# front_pcb.net
KiCad netlist of a schematic drawn in EAGLE
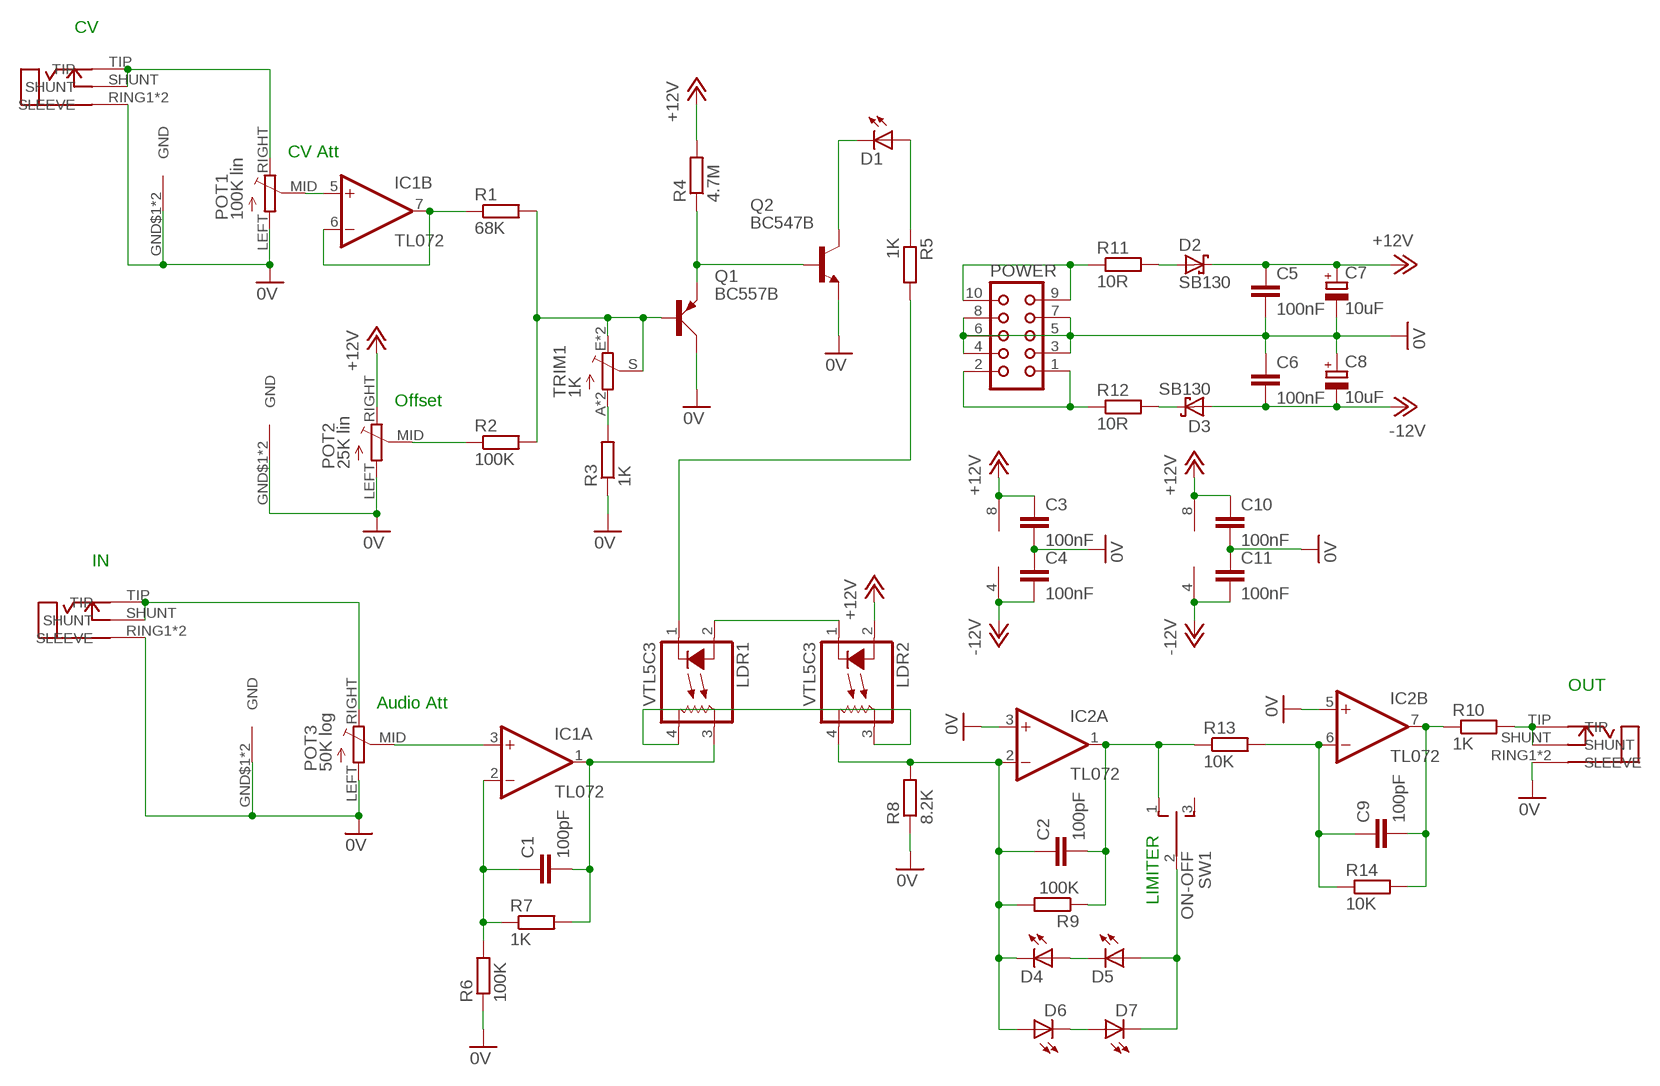
[diagram p0: schematic, sheet 1]

(export (version "E")
  (design (tool "Eeschema 10.0.6"))
  (components
    (comp (ref "C1")
      (value "100pF")
      (footprint "eagle-import:C025-024X044")
      (libsource (lib "eagle-import") (part "C-EU025-024X044"))
    )
    (comp (ref "C2")
      (value "100pF")
      (footprint "eagle-import:C025-024X044")
      (libsource (lib "eagle-import") (part "C-EU025-024X044"))
    )
    (comp (ref "C3")
      (value "100nF")
      (footprint "eagle-import:C025-024X044")
      (libsource (lib "eagle-import") (part "C-EU025-024X044"))
    )
    (comp (ref "C4")
      (value "100nF")
      (footprint "eagle-import:C025-024X044")
      (libsource (lib "eagle-import") (part "C-EU025-024X044"))
    )
    (comp (ref "C5")
      (value "100nF")
      (footprint "eagle-import:C025-024X044")
      (libsource (lib "eagle-import") (part "C-EU025-024X044"))
    )
    (comp (ref "C6")
      (value "100nF")
      (footprint "eagle-import:C025-024X044")
      (libsource (lib "eagle-import") (part "C-EU025-024X044"))
    )
    (comp (ref "C7")
      (value "10uF")
      (footprint "eagle-import:E2-5")
      (libsource (lib "eagle-import") (part "CPOL-EUE2-5"))
    )
    (comp (ref "C8")
      (value "10uF")
      (footprint "eagle-import:E2-5")
      (libsource (lib "eagle-import") (part "CPOL-EUE2-5"))
    )
    (comp (ref "C9")
      (value "100pF")
      (footprint "eagle-import:C025-024X044")
      (libsource (lib "eagle-import") (part "C-EU025-024X044"))
    )
    (comp (ref "C10")
      (value "100nF")
      (footprint "eagle-import:C025-024X044")
      (libsource (lib "eagle-import") (part "C-EU025-024X044"))
    )
    (comp (ref "C11")
      (value "100nF")
      (footprint "eagle-import:C025-024X044")
      (libsource (lib "eagle-import") (part "C-EU025-024X044"))
    )
    (comp (ref "CV")
      (value "ERTHENVAR_3.5MM_JACK")
      (footprint "eagle-import:ERTHENVAR")
      (libsource (lib "eagle-import") (part "ERTHENVAR_3.5MM_JACK"))
    )
    (comp (ref "D1")
      (value "LED3MM")
      (footprint "eagle-import:LED3MM")
      (libsource (lib "eagle-import") (part "LED3MM"))
    )
    (comp (ref "D2")
      (value "SB130")
      (footprint "eagle-import:DO41-7")
      (libsource (lib "eagle-import") (part "SB130DO-204AL"))
    )
    (comp (ref "D3")
      (value "SB130")
      (footprint "eagle-import:DO41-7")
      (libsource (lib "eagle-import") (part "SB130DO-204AL"))
    )
    (comp (ref "D4")
      (value "LED3MM")
      (footprint "eagle-import:LED3MM")
      (libsource (lib "eagle-import") (part "LED3MM"))
    )
    (comp (ref "D5")
      (value "LED3MM")
      (footprint "eagle-import:LED3MM")
      (libsource (lib "eagle-import") (part "LED3MM"))
    )
    (comp (ref "D6")
      (value "LED3MM")
      (footprint "eagle-import:LED3MM")
      (libsource (lib "eagle-import") (part "LED3MM"))
    )
    (comp (ref "D7")
      (value "LED3MM")
      (footprint "eagle-import:LED3MM")
      (libsource (lib "eagle-import") (part "LED3MM"))
    )
    (comp (ref "IC1")
      (value "TL072")
      (footprint "eagle-import:DIL08")
      (libsource (lib "eagle-import") (part "TL072P"))
    )
    (comp (ref "IC2")
      (value "TL072")
      (footprint "eagle-import:DIL08")
      (libsource (lib "eagle-import") (part "TL072P"))
    )
    (comp (ref "IN")
      (value "ERTHENVAR_3.5MM_JACK")
      (footprint "eagle-import:ERTHENVAR")
      (libsource (lib "eagle-import") (part "ERTHENVAR_3.5MM_JACK"))
    )
    (comp (ref "LDR1")
      (value "VTL5C3")
      (footprint "eagle-import:VTL5C")
      (fields (field (name "MF") "VACTEC PHOTO") (field (name "MPN") "VTL5C9"))
      (libsource (lib "eagle-import") (part "VTL5C9"))
    )
    (comp (ref "LDR2")
      (value "VTL5C3")
      (footprint "eagle-import:VTL5C")
      (fields (field (name "MF") "VACTEC PHOTO") (field (name "MPN") "VTL5C9"))
      (libsource (lib "eagle-import") (part "VTL5C9"))
    )
    (comp (ref "OUT")
      (value "ERTHENVAR_3.5MM_JACK")
      (footprint "eagle-import:ERTHENVAR")
      (libsource (lib "eagle-import") (part "ERTHENVAR_3.5MM_JACK"))
    )
    (comp (ref "POT1")
      (value "100K lin")
      (footprint "eagle-import:POT-ALPHA9")
      (libsource (lib "eagle-import") (part "POT-ALPHA9"))
    )
    (comp (ref "POT2")
      (value "25K lin")
      (footprint "eagle-import:POT-ALPHA9")
      (libsource (lib "eagle-import") (part "POT-ALPHA9"))
    )
    (comp (ref "POT3")
      (value "50K log")
      (footprint "eagle-import:POT-ALPHA9")
      (libsource (lib "eagle-import") (part "POT-ALPHA9"))
    )
    (comp (ref "POWER")
      (value "CON10L")
      (footprint "eagle-import:CON10L")
      (libsource (lib "eagle-import") (part "CON10L"))
    )
    (comp (ref "Q1")
      (value "BC557B")
      (footprint "eagle-import:TO92-LINE")
      (libsource (lib "eagle-import") (part "BC557TO92-LINE"))
    )
    (comp (ref "Q2")
      (value "BC547B")
      (footprint "eagle-import:TO92-LINE")
      (libsource (lib "eagle-import") (part "BC547TO92-LINE"))
    )
    (comp (ref "R1")
      (value "68K")
      (footprint "eagle-import:0207_9")
      (libsource (lib "eagle-import") (part "R-EU_0207/10"))
    )
    (comp (ref "R2")
      (value "100K")
      (footprint "eagle-import:0207_9")
      (libsource (lib "eagle-import") (part "R-EU_0207/10"))
    )
    (comp (ref "R3")
      (value "1K")
      (footprint "eagle-import:0207_9")
      (libsource (lib "eagle-import") (part "R-EU_0207/10"))
    )
    (comp (ref "R4")
      (value "4.7M")
      (footprint "eagle-import:0207_9")
      (libsource (lib "eagle-import") (part "R-EU_0207/10"))
    )
    (comp (ref "R5")
      (value "1K")
      (footprint "eagle-import:0207_9")
      (libsource (lib "eagle-import") (part "R-EU_0207/10"))
    )
    (comp (ref "R6")
      (value "100K")
      (footprint "eagle-import:0207_9")
      (libsource (lib "eagle-import") (part "R-EU_0207/10"))
    )
    (comp (ref "R7")
      (value "1K")
      (footprint "eagle-import:0207_9")
      (libsource (lib "eagle-import") (part "R-EU_0207/10"))
    )
    (comp (ref "R8")
      (value "8.2K")
      (footprint "eagle-import:0207_9")
      (libsource (lib "eagle-import") (part "R-EU_0207/10"))
    )
    (comp (ref "R9")
      (value "100K")
      (footprint "eagle-import:0207_9")
      (libsource (lib "eagle-import") (part "R-EU_0207/10"))
    )
    (comp (ref "R10")
      (value "1K")
      (footprint "eagle-import:0207_9")
      (libsource (lib "eagle-import") (part "R-EU_0207/10"))
    )
    (comp (ref "R11")
      (value "10R")
      (footprint "eagle-import:0207_9")
      (libsource (lib "eagle-import") (part "R-EU_0207/10"))
    )
    (comp (ref "R12")
      (value "10R")
      (footprint "eagle-import:0207_9")
      (libsource (lib "eagle-import") (part "R-EU_0207/10"))
    )
    (comp (ref "R13")
      (value "10K")
      (footprint "eagle-import:0207_9")
      (libsource (lib "eagle-import") (part "R-EU_0207/10"))
    )
    (comp (ref "R14")
      (value "10K")
      (footprint "eagle-import:0207_9")
      (libsource (lib "eagle-import") (part "R-EU_0207/10"))
    )
    (comp (ref "SW1")
      (value "ON-OFF")
      (footprint "eagle-import:SPDT-HORIZONTAL-TOP-SUBMINI-MULTICOMP")
      (libsource (lib "eagle-import") (part "SPDTTOP-SUBMINI"))
    )
    (comp (ref "TRIM1")
      (value "1K")
      (footprint "eagle-import:B25P")
      (libsource (lib "eagle-import") (part "TRIM_EU-B25P"))
    )
  )
  (nets
    (net (code "1") (name "+12V") (class "Default")
      (node (ref "C10") (pin "1") (pinfunction "1_1") (pintype "passive"))
      (node (ref "C3") (pin "1") (pinfunction "1_1") (pintype "passive"))
      (node (ref "C5") (pin "1") (pinfunction "1_1") (pintype "passive"))
      (node (ref "C7") (pin "+") (pinfunction "+_+") (pintype "passive"))
      (node (ref "D2") (pin "C") (pinfunction "C_C") (pintype "passive"))
      (node (ref "IC1") (pin "8") (pinfunction "V+_8") (pintype "power_in"))
      (node (ref "IC2") (pin "8") (pinfunction "V+_8") (pintype "power_in"))
      (node (ref "LDR2") (pin "2") (pinfunction "A_2") (pintype "passive"))
      (node (ref "POT2") (pin "RIGHT") (pinfunction "RIGHT_RIGHT") (pintype "passive"))
      (node (ref "R4") (pin "2") (pinfunction "2_2") (pintype "passive"))
    )
    (net (code "2") (name "-12V") (class "Default")
      (node (ref "C11") (pin "2") (pinfunction "2_2") (pintype "passive"))
      (node (ref "C4") (pin "2") (pinfunction "2_2") (pintype "passive"))
      (node (ref "C6") (pin "2") (pinfunction "2_2") (pintype "passive"))
      (node (ref "C8") (pin "-") (pinfunction "-_-") (pintype "passive"))
      (node (ref "D3") (pin "A") (pinfunction "A_A") (pintype "passive"))
      (node (ref "IC1") (pin "4") (pinfunction "V-_4") (pintype "power_in"))
      (node (ref "IC2") (pin "4") (pinfunction "V-_4") (pintype "power_in"))
    )
    (net (code "3") (name "0V") (class "Default")
      (node (ref "C10") (pin "2") (pinfunction "2_2") (pintype "passive"))
      (node (ref "C11") (pin "1") (pinfunction "1_1") (pintype "passive"))
      (node (ref "C3") (pin "2") (pinfunction "2_2") (pintype "passive"))
      (node (ref "C4") (pin "1") (pinfunction "1_1") (pintype "passive"))
      (node (ref "C5") (pin "2") (pinfunction "2_2") (pintype "passive"))
      (node (ref "C6") (pin "1") (pinfunction "1_1") (pintype "passive"))
      (node (ref "C7") (pin "-") (pinfunction "-_-") (pintype "passive"))
      (node (ref "C8") (pin "+") (pinfunction "+_+") (pintype "passive"))
      (node (ref "CV") (pin "RING1") (pinfunction "SLEEVE_RING1") (pintype "bidirectional"))
      (node (ref "CV") (pin "RING2") (pinfunction "SLEEVE_RING2") (pintype "bidirectional"))
      (node (ref "IC2") (pin "3") (pinfunction "+IN_3") (pintype "input"))
      (node (ref "IC2") (pin "5") (pinfunction "+IN_5") (pintype "input"))
      (node (ref "IN") (pin "RING1") (pinfunction "SLEEVE_RING1") (pintype "bidirectional"))
      (node (ref "IN") (pin "RING2") (pinfunction "SLEEVE_RING2") (pintype "bidirectional"))
      (node (ref "OUT") (pin "RING1") (pinfunction "SLEEVE_RING1") (pintype "bidirectional"))
      (node (ref "OUT") (pin "RING2") (pinfunction "SLEEVE_RING2") (pintype "bidirectional"))
      (node (ref "POT1") (pin "GND$1") (pinfunction "GND_GND$1") (pintype "bidirectional"))
      (node (ref "POT1") (pin "GND$2") (pinfunction "GND_GND$2") (pintype "bidirectional"))
      (node (ref "POT1") (pin "LEFT") (pinfunction "LEFT_LEFT") (pintype "passive"))
      (node (ref "POT2") (pin "GND$1") (pinfunction "GND_GND$1") (pintype "bidirectional"))
      (node (ref "POT2") (pin "GND$2") (pinfunction "GND_GND$2") (pintype "bidirectional"))
      (node (ref "POT2") (pin "LEFT") (pinfunction "LEFT_LEFT") (pintype "passive"))
      (node (ref "POT3") (pin "GND$1") (pinfunction "GND_GND$1") (pintype "bidirectional"))
      (node (ref "POT3") (pin "GND$2") (pinfunction "GND_GND$2") (pintype "bidirectional"))
      (node (ref "POT3") (pin "LEFT") (pinfunction "LEFT_LEFT") (pintype "passive"))
      (node (ref "POWER") (pin "3") (pinfunction "3_3") (pintype "passive"))
      (node (ref "POWER") (pin "4") (pinfunction "4_4") (pintype "passive"))
      (node (ref "POWER") (pin "5") (pinfunction "5_5") (pintype "passive"))
      (node (ref "POWER") (pin "6") (pinfunction "6_6") (pintype "passive"))
      (node (ref "POWER") (pin "7") (pinfunction "7_7") (pintype "passive"))
      (node (ref "POWER") (pin "8") (pinfunction "8_8") (pintype "passive"))
      (node (ref "Q1") (pin "3") (pinfunction "C_3") (pintype "passive"))
      (node (ref "Q2") (pin "1") (pinfunction "E_1") (pintype "passive"))
      (node (ref "R3") (pin "1") (pinfunction "1_1") (pintype "passive"))
      (node (ref "R6") (pin "1") (pinfunction "1_1") (pintype "passive"))
      (node (ref "R8") (pin "1") (pinfunction "1_1") (pintype "passive"))
    )
    (net (code "4") (name "Net-(CV-PadSHUNT)") (class "Default")
      (node (ref "CV") (pin "SHUNT") (pinfunction "SHUNT_SHUNT") (pintype "bidirectional"))
      (node (ref "CV") (pin "TIP") (pinfunction "TIP_TIP") (pintype "bidirectional"))
      (node (ref "POT1") (pin "RIGHT") (pinfunction "RIGHT_RIGHT") (pintype "passive"))
    )
    (net (code "5") (name "Net-(D1-C)") (class "Default")
      (node (ref "D1") (pin "K") (pinfunction "C_K") (pintype "passive"))
      (node (ref "Q2") (pin "3") (pinfunction "C_3") (pintype "passive"))
    )
    (net (code "6") (name "Net-(D1-PadA)") (class "Default")
      (node (ref "D1") (pin "A") (pinfunction "A_A") (pintype "passive"))
      (node (ref "R5") (pin "1") (pinfunction "1_1") (pintype "passive"))
    )
    (net (code "7") (name "Net-(D2-PadA)") (class "Default")
      (node (ref "D2") (pin "A") (pinfunction "A_A") (pintype "passive"))
      (node (ref "R11") (pin "2") (pinfunction "2_2") (pintype "passive"))
    )
    (net (code "8") (name "Net-(D3-PadC)") (class "Default")
      (node (ref "D3") (pin "C") (pinfunction "C_C") (pintype "passive"))
      (node (ref "R12") (pin "2") (pinfunction "2_2") (pintype "passive"))
    )
    (net (code "9") (name "Net-(D4-C)") (class "Default")
      (node (ref "C2") (pin "1") (pinfunction "1_1") (pintype "passive"))
      (node (ref "D4") (pin "K") (pinfunction "C_K") (pintype "passive"))
      (node (ref "D6") (pin "A") (pinfunction "A_A") (pintype "passive"))
      (node (ref "IC2") (pin "2") (pinfunction "-IN_2") (pintype "input"))
      (node (ref "LDR2") (pin "4") (pinfunction "L2_4") (pintype "passive"))
      (node (ref "R8") (pin "2") (pinfunction "2_2") (pintype "passive"))
      (node (ref "R9") (pin "2") (pinfunction "2_2") (pintype "passive"))
    )
    (net (code "10") (name "Net-(D5-C)") (class "Default")
      (node (ref "D4") (pin "A") (pinfunction "A_A") (pintype "passive"))
      (node (ref "D5") (pin "K") (pinfunction "C_K") (pintype "passive"))
    )
    (net (code "11") (name "Net-(D6-C)") (class "Default")
      (node (ref "D6") (pin "K") (pinfunction "C_K") (pintype "passive"))
      (node (ref "D7") (pin "A") (pinfunction "A_A") (pintype "passive"))
    )
    (net (code "12") (name "Net-(D7-C)") (class "Default")
      (node (ref "D5") (pin "A") (pinfunction "A_A") (pintype "passive"))
      (node (ref "D7") (pin "K") (pinfunction "C_K") (pintype "passive"))
      (node (ref "SW1") (pin "2") (pinfunction "2_2") (pintype "passive"))
    )
    (net (code "13") (name "Net-(IC1A-+IN)") (class "Default")
      (node (ref "IC1") (pin "3") (pinfunction "+IN_3") (pintype "input"))
      (node (ref "POT3") (pin "MID") (pinfunction "MID_MID") (pintype "passive"))
    )
    (net (code "14") (name "Net-(IC1A--IN)") (class "Default")
      (node (ref "C1") (pin "1") (pinfunction "1_1") (pintype "passive"))
      (node (ref "IC1") (pin "2") (pinfunction "-IN_2") (pintype "input"))
      (node (ref "R6") (pin "2") (pinfunction "2_2") (pintype "passive"))
      (node (ref "R7") (pin "1") (pinfunction "1_1") (pintype "passive"))
    )
    (net (code "15") (name "Net-(IC1A-OUT)") (class "Default")
      (node (ref "C1") (pin "2") (pinfunction "2_2") (pintype "passive"))
      (node (ref "IC1") (pin "1") (pinfunction "OUT_1") (pintype "output"))
      (node (ref "LDR1") (pin "3") (pinfunction "L1_3") (pintype "passive"))
      (node (ref "R7") (pin "2") (pinfunction "2_2") (pintype "passive"))
    )
    (net (code "16") (name "Net-(IC1B-+IN)") (class "Default")
      (node (ref "IC1") (pin "5") (pinfunction "+IN_5") (pintype "input"))
      (node (ref "POT1") (pin "MID") (pinfunction "MID_MID") (pintype "passive"))
    )
    (net (code "17") (name "Net-(IC1B--IN)") (class "Default")
      (node (ref "IC1") (pin "6") (pinfunction "-IN_6") (pintype "input"))
      (node (ref "IC1") (pin "7") (pinfunction "OUT_7") (pintype "output"))
      (node (ref "R1") (pin "1") (pinfunction "1_1") (pintype "passive"))
    )
    (net (code "18") (name "Net-(IC2A-OUT)") (class "Default")
      (node (ref "C2") (pin "2") (pinfunction "2_2") (pintype "passive"))
      (node (ref "IC2") (pin "1") (pinfunction "OUT_1") (pintype "output"))
      (node (ref "R13") (pin "1") (pinfunction "1_1") (pintype "passive"))
      (node (ref "R9") (pin "1") (pinfunction "1_1") (pintype "passive"))
      (node (ref "SW1") (pin "1") (pinfunction "1_1") (pintype "passive"))
    )
    (net (code "19") (name "Net-(IC2B--IN)") (class "Default")
      (node (ref "C9") (pin "1") (pinfunction "1_1") (pintype "passive"))
      (node (ref "IC2") (pin "6") (pinfunction "-IN_6") (pintype "input"))
      (node (ref "R13") (pin "2") (pinfunction "2_2") (pintype "passive"))
      (node (ref "R14") (pin "1") (pinfunction "1_1") (pintype "passive"))
    )
    (net (code "20") (name "Net-(IC2B-OUT)") (class "Default")
      (node (ref "C9") (pin "2") (pinfunction "2_2") (pintype "passive"))
      (node (ref "IC2") (pin "7") (pinfunction "OUT_7") (pintype "output"))
      (node (ref "R10") (pin "1") (pinfunction "1_1") (pintype "passive"))
      (node (ref "R14") (pin "2") (pinfunction "2_2") (pintype "passive"))
    )
    (net (code "21") (name "Net-(IN-PadSHUNT)") (class "Default")
      (node (ref "IN") (pin "SHUNT") (pinfunction "SHUNT_SHUNT") (pintype "bidirectional"))
      (node (ref "IN") (pin "TIP") (pinfunction "TIP_TIP") (pintype "bidirectional"))
      (node (ref "POT3") (pin "RIGHT") (pinfunction "RIGHT_RIGHT") (pintype "passive"))
    )
    (net (code "22") (name "Net-(LDR1-A)") (class "Default")
      (node (ref "LDR1") (pin "2") (pinfunction "A_2") (pintype "passive"))
      (node (ref "LDR2") (pin "1") (pinfunction "C_1") (pintype "passive"))
    )
    (net (code "23") (name "Net-(LDR1-C)") (class "Default")
      (node (ref "LDR1") (pin "1") (pinfunction "C_1") (pintype "passive"))
      (node (ref "R5") (pin "2") (pinfunction "2_2") (pintype "passive"))
    )
    (net (code "24") (name "Net-(LDR1-L2)") (class "Default")
      (node (ref "LDR1") (pin "4") (pinfunction "L2_4") (pintype "passive"))
      (node (ref "LDR2") (pin "3") (pinfunction "L1_3") (pintype "passive"))
    )
    (net (code "25") (name "Net-(OUT-PadSHUNT)") (class "Default")
      (node (ref "OUT") (pin "SHUNT") (pinfunction "SHUNT_SHUNT") (pintype "bidirectional"))
      (node (ref "OUT") (pin "TIP") (pinfunction "TIP_TIP") (pintype "bidirectional"))
      (node (ref "R10") (pin "2") (pinfunction "2_2") (pintype "passive"))
    )
    (net (code "26") (name "Net-(POT2-PadMID)") (class "Default")
      (node (ref "POT2") (pin "MID") (pinfunction "MID_MID") (pintype "passive"))
      (node (ref "R2") (pin "1") (pinfunction "1_1") (pintype "passive"))
    )
    (net (code "27") (name "Net-(POWER-Pad1)") (class "Default")
      (node (ref "POWER") (pin "1") (pinfunction "1_1") (pintype "passive"))
      (node (ref "POWER") (pin "2") (pinfunction "2_2") (pintype "passive"))
      (node (ref "R12") (pin "1") (pinfunction "1_1") (pintype "passive"))
    )
    (net (code "28") (name "Net-(POWER-Pad10)") (class "Default")
      (node (ref "POWER") (pin "10") (pinfunction "10_10") (pintype "passive"))
      (node (ref "POWER") (pin "9") (pinfunction "9_9") (pintype "passive"))
      (node (ref "R11") (pin "1") (pinfunction "1_1") (pintype "passive"))
    )
    (net (code "29") (name "Net-(Q1-B)") (class "Default")
      (node (ref "Q1") (pin "2") (pinfunction "B_2") (pintype "passive"))
      (node (ref "R1") (pin "2") (pinfunction "2_2") (pintype "passive"))
      (node (ref "R2") (pin "2") (pinfunction "2_2") (pintype "passive"))
      (node (ref "TRIM1") (pin "E") (pinfunction "E_E") (pintype "passive"))
      (node (ref "TRIM1") (pin "EE") (pinfunction "E_EE") (pintype "passive"))
      (node (ref "TRIM1") (pin "S") (pinfunction "S_S") (pintype "passive"))
    )
    (net (code "30") (name "Net-(Q1-E)") (class "Default")
      (node (ref "Q1") (pin "1") (pinfunction "E_1") (pintype "passive"))
      (node (ref "Q2") (pin "2") (pinfunction "B_2") (pintype "passive"))
      (node (ref "R4") (pin "1") (pinfunction "1_1") (pintype "passive"))
    )
    (net (code "31") (name "Net-(R3-Pad2)") (class "Default")
      (node (ref "R3") (pin "2") (pinfunction "2_2") (pintype "passive"))
      (node (ref "TRIM1") (pin "A") (pinfunction "A_A") (pintype "passive"))
      (node (ref "TRIM1") (pin "AA") (pinfunction "A_AA") (pintype "passive"))
    )
    (net (code "32") (name "unconnected-(SW1-Pad3)") (class "Default")
      (node (ref "SW1") (pin "3") (pinfunction "3_3") (pintype "passive"))
    )
  )
)
